# Sheet1.net
KiCad netlist of a schematic drawn in Altium Designer
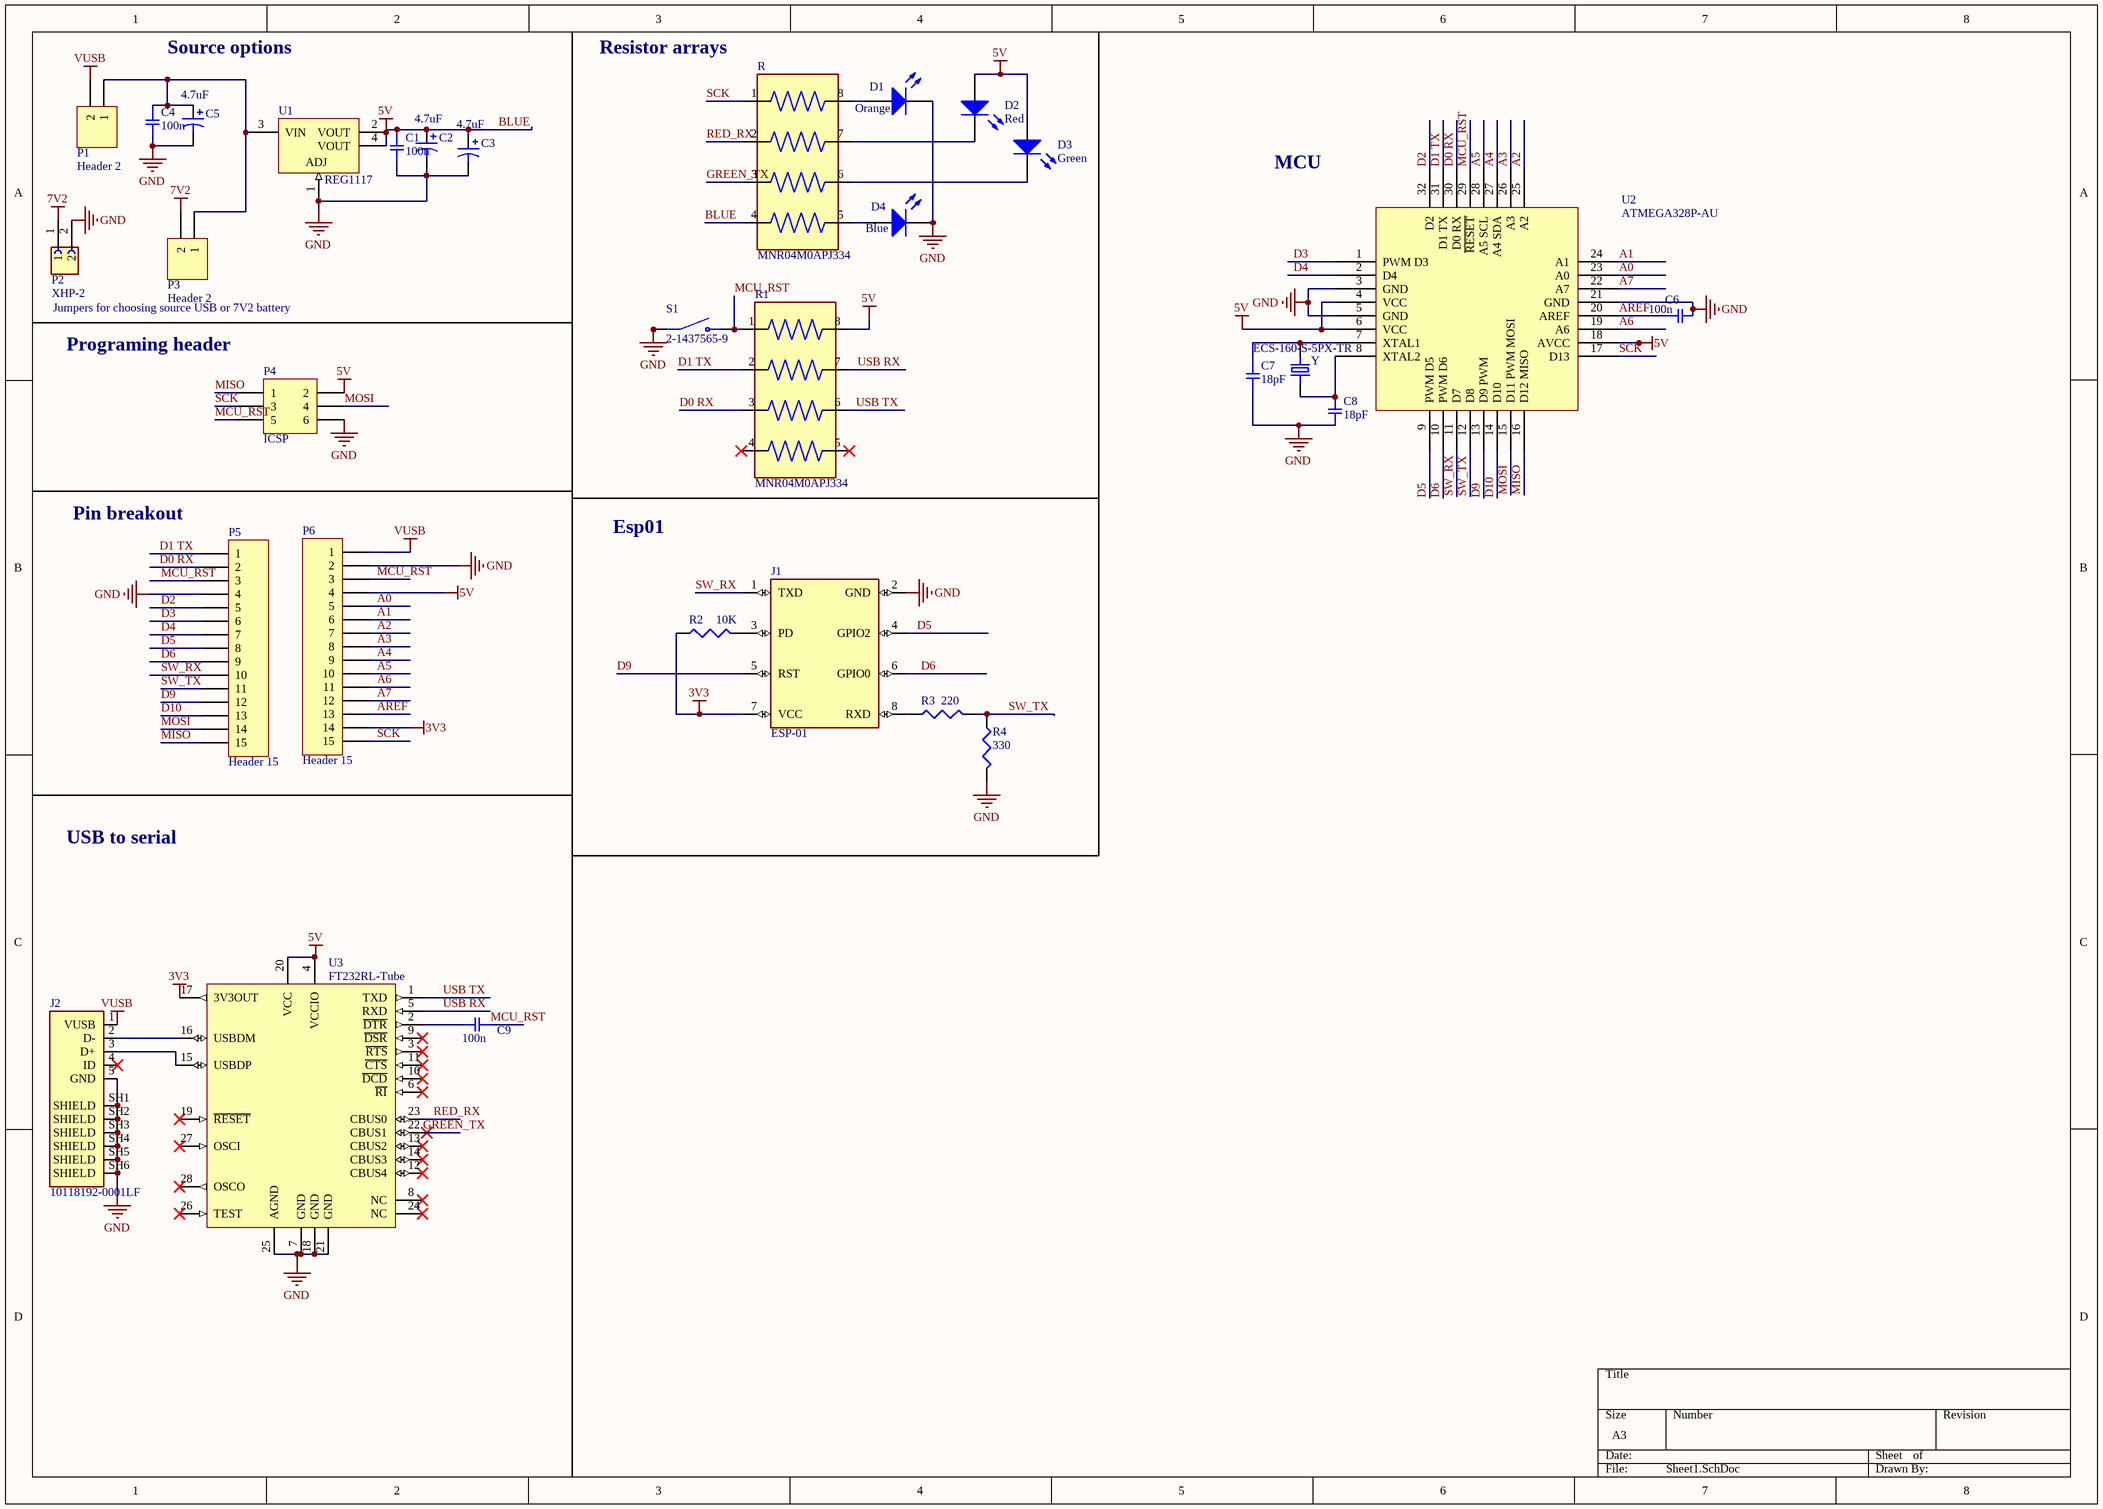
[diagram p0: Sheet1.SchDoc]

(export (version "E")
  (design (tool "Eeschema 10.0.6"))
  (components
    (comp (ref "C1")
      (value "100n")
      (footprint "SMD-0805C")
      (description "CAP CER 18PF 100V NP0 0805")
      (fields
        (field (name "DIGI-KEY PART NUMBER") "490-3606-1-ND")
        (field (name "PART NUMBER") "GQM2195C2A180JB01D")
      )
      (libsource (lib "capacitor_murata_0805") (part "GQM2195C2A180JB01D"))
    )
    (comp (ref "C2")
      (value "4.7uF")
      (footprint "49BC-E")
      (fields (field (name "Comment") "49BC475B010M") (field (name "PUBLISHER") "Altium Limited"))
      (libsource (lib "Vishay Sprague Tantalum Chip Capacitor") (part "49BC475B010M"))
    )
    (comp (ref "C3")
      (value "4.7uF")
      (footprint "49BC-E")
      (fields (field (name "Comment") "49BC475B010M") (field (name "PUBLISHER") "Altium Limited"))
      (libsource (lib "Vishay Sprague Tantalum Chip Capacitor") (part "49BC475B010M"))
    )
    (comp (ref "C4")
      (value "100n")
      (footprint "SMD-0805C")
      (description "CAP CER 18PF 100V NP0 0805")
      (fields
        (field (name "DIGI-KEY PART NUMBER") "490-3606-1-ND")
        (field (name "PART NUMBER") "GQM2195C2A180JB01D")
      )
      (libsource (lib "capacitor_murata_0805") (part "GQM2195C2A180JB01D"))
    )
    (comp (ref "C5")
      (value "4.7uF")
      (footprint "49BC-E")
      (fields (field (name "Comment") "49BC475B010M") (field (name "PUBLISHER") "Altium Limited"))
      (libsource (lib "Vishay Sprague Tantalum Chip Capacitor") (part "49BC475B010M"))
    )
    (comp (ref "C6")
      (value "100n")
      (footprint "SMD-0805C")
      (description "CAP CER 18PF 100V NP0 0805")
      (fields
        (field (name "DIGI-KEY PART NUMBER") "490-3606-1-ND")
        (field (name "PART NUMBER") "GQM2195C2A180JB01D")
      )
      (libsource (lib "capacitor_murata_0805") (part "GQM2195C2A180JB01D"))
    )
    (comp (ref "C7")
      (value "18pF")
      (footprint "SMD-0805C")
      (description "CAP CER 18PF 100V NP0 0805")
      (fields
        (field (name "DIGI-KEY PART NUMBER") "490-3606-1-ND")
        (field (name "PART NUMBER") "GQM2195C2A180JB01D")
      )
      (libsource (lib "capacitor_murata_0805") (part "GQM2195C2A180JB01D"))
    )
    (comp (ref "C8")
      (value "18pF")
      (footprint "SMD-0805C")
      (description "CAP CER 18PF 100V NP0 0805")
      (fields
        (field (name "DIGI-KEY PART NUMBER") "490-3606-1-ND")
        (field (name "PART NUMBER") "GQM2195C2A180JB01D")
      )
      (libsource (lib "capacitor_murata_0805") (part "GQM2195C2A180JB01D"))
    )
    (comp (ref "C9")
      (value "100n")
      (footprint "SMD-0805C")
      (description "CAP CER 18PF 100V NP0 0805")
      (fields
        (field (name "DIGI-KEY PART NUMBER") "490-3606-1-ND")
        (field (name "PART NUMBER") "GQM2195C2A180JB01D")
      )
      (libsource (lib "capacitor_murata_0805") (part "GQM2195C2A180JB01D"))
    )
    (comp (ref "D1")
      (value "Orange")
      (footprint "2.0X1.25X0.8")
      (fields (field (name "PUBLISHER") "Altium Limited"))
      (libsource (lib "Avago Optoelectronic LED") (part "HSMQ-C170"))
    )
    (comp (ref "D2")
      (value "Red")
      (footprint "2.0X1.25X0.8")
      (description "SMT Top Mount Chip LED, Green")
      (fields (field (name "PUBLISHER") "Altium Limited"))
      (libsource (lib "Avago Optoelectronic LED") (part "HSMQ-C170"))
    )
    (comp (ref "D3")
      (value "Green")
      (footprint "2.0X1.25X0.8")
      (description "SMT Top Mount Chip LED, Green")
      (fields (field (name "PUBLISHER") "Altium Limited"))
      (libsource (lib "Avago Optoelectronic LED") (part "HSMQ-C170"))
    )
    (comp (ref "D4")
      (value "Blue")
      (footprint "2.0X1.25X0.8")
      (description "SMT Top Mount Chip LED, Green")
      (fields (field (name "PUBLISHER") "Altium Limited"))
      (libsource (lib "Avago Optoelectronic LED") (part "HSMQ-C170"))
    )
    (comp (ref "J1")
      (value "ESP-01")
      (footprint "ESP-01:ESP-01")
      (description "ESP-01M ESP8266 DIP Adapter series Transceiver; 802.11 b/g/n (Wi-Fi, WiFi, WLAN) Evaluation Board")
      (fields (field (name "MF") "AI-Thinker"))
      (libsource (lib "ESP-01") (part "ESP-01"))
    )
    (comp (ref "J2")
      (value "10118192-0001LF")
      (footprint "AMPHENOL_10118192-0001LF")
      (description "Micro USB, Input Output Connectors, B TYPE RECEPTACLE with flange")
      (fields (field (name "MF") "AMPHENOL ICC / FCI"))
      (libsource (lib "10118192-0001LF") (part "10118192-0001LF"))
    )
    (comp (ref "P1")
      (value "Header 2")
      (footprint "HDR1X2")
      (description "Header, 2-Pin")
      (fields (field (name "PUBLISHER") "Altium Limited"))
      (libsource (lib "Miscellaneous Connectors") (part "Header 2"))
    )
    (comp (ref "P2")
      (value "XHP-2")
      (footprint "JST_XHP-2")
      (description "XH Series 2 Position 2.5 mm Pitch Wire-to-Board Housing Connector")
      (libsource (lib "XHP-2") (part "XHP-2"))
    )
    (comp (ref "P3")
      (value "Header 2")
      (footprint "HDR1X2")
      (description "Header, 2-Pin")
      (fields (field (name "PUBLISHER") "Altium Limited"))
      (libsource (lib "Miscellaneous Connectors") (part "Header 2"))
    )
    (comp (ref "P4")
      (value "ICSP")
      (footprint "HDR2X3")
      (description "Header, 3-Pin, Dual row")
      (fields (field (name "PUBLISHER") "Altium Limited"))
      (libsource (lib "Miscellaneous Connectors") (part "Header 3X2"))
    )
    (comp (ref "P5")
      (value "Header 15")
      (footprint "HDR1X15")
      (description "Header, 15-Pin")
      (fields (field (name "PUBLISHER") "Altium Limited"))
      (libsource (lib "Miscellaneous Connectors") (part "Header 15"))
    )
    (comp (ref "P6")
      (value "Header 15")
      (footprint "HDR1X15")
      (description "Header, 15-Pin")
      (fields (field (name "PUBLISHER") "Altium Limited"))
      (libsource (lib "") (part "Header 15_1"))
    )
    (comp (ref "R")
      (value "MNR04M0APJ334")
      (footprint "RESCAXS50P200X100X45-8N:RESCAXS50P200X100X45-8N")
      (description "Res Array 330K Ohm 5% Â±200ppm/Â°C ISOL Epoxy 8-Pin 0804(4 X 0402) Convex SMD Automotive T/R")
      (fields (field (name "MF") "Rohm"))
      (libsource (lib "MNR04M0APJ334") (part "MNR04M0APJ334"))
    )
    (comp (ref "R1")
      (value "MNR04M0APJ334")
      (footprint "RESCAXS50P200X100X45-8N:RESCAXS50P200X100X45-8N")
      (description "Res Array 330K Ohm 5% Â±200ppm/Â°C ISOL Epoxy 8-Pin 0804(4 X 0402) Convex SMD Automotive T/R")
      (fields (field (name "MF") "Rohm"))
      (libsource (lib "MNR04M0APJ334") (part "MNR04M0APJ334"))
    )
    (comp (ref "R2")
      (value "10K")
      (footprint "J1-0603")
      (description "Resistor")
      (fields (field (name "Comment") "Res3") (field (name "PUBLISHER") "Altium Limited"))
      (libsource (lib "Miscellaneous Devices") (part "Res3"))
    )
    (comp (ref "R3")
      (value "220")
      (footprint "J1-0603")
      (description "Resistor")
      (fields (field (name "Comment") "Res3") (field (name "PUBLISHER") "Altium Limited"))
      (libsource (lib "Miscellaneous Devices") (part "Res3"))
    )
    (comp (ref "R4")
      (value "330")
      (footprint "J1-0603")
      (description "Resistor")
      (fields (field (name "Comment") "Res3") (field (name "PUBLISHER") "Altium Limited"))
      (libsource (lib "Miscellaneous Devices") (part "Res3"))
    )
    (comp (ref "S1")
      (value "2-1437565-9")
      (footprint "SW_2-1437565-9")
      (fields (field (name "MF") "{'manufacturer': 'TE Connectivity'}"))
      (libsource (lib "2-1437565-9") (part "2-1437565-9"))
    )
    (comp (ref "U1")
      (value "REG1117")
      (footprint "TI-DCY4_N")
      (fields (field (name "MANUFACTURER") "Texas Instruments"))
      (libsource (lib "TI Power Management Linear Regulator Single Channel LDO (400-7500mA)") (part "REG1117"))
    )
    (comp (ref "U2")
      (value "ATMEGA328P-AU")
      (footprint "TQFP80P900X900X120-32N")
      (description "Microchip ATMEGA328P-AU, 8bit AVR Microcontroller, ATmega, 20MHz, 32 kB Flash, 32-Pin TQFP")
      (fields (field (name "CREATED BY") "Mariano Franceschetti"))
      (libsource (lib "AtmelMCU") (part "ATMEGA328P-AU"))
    )
    (comp (ref "U3")
      (value "FT232RL-Tube")
      (footprint "SSOP-28_N")
      (description "USB UART Asynchronous Serial Data Transfer Chip, SSOP-28, Tube")
      (fields (field (name "PUBLISHER") "Altium Limited"))
      (libsource (lib "FTDI Communication UART") (part "FT232RL-Tube"))
    )
    (comp (ref "Y")
      (value "ECS-160-S-5PX-TR")
      (footprint "SnapEDApcb:XTAL_ECS-160-S-5PX-TR")
      (description "16MHz Â±30ppm Crystal Series 40 Ohms HC-49/US")
      (fields (field (name "MF") "ECS Inc."))
      (libsource (lib "ECS-160-S-5PX-TR") (part "ECS-160-S-5PX-TR"))
    )
  )
  (nets
    (net (code "1") (name "/A0") (class "Default")
      (node (ref "P6") (pin "5") (pinfunction "5_5") (pintype "passive"))
      (node (ref "U2") (pin "23") (pinfunction "A0_23") (pintype "power_in"))
    )
    (net (code "2") (name "/A1") (class "Default")
      (node (ref "P6") (pin "6") (pinfunction "6_6") (pintype "passive"))
      (node (ref "U2") (pin "24") (pinfunction "A1_24") (pintype "power_in"))
    )
    (net (code "3") (name "/A2") (class "Default")
      (node (ref "P6") (pin "7") (pinfunction "7_7") (pintype "passive"))
      (node (ref "U2") (pin "25") (pinfunction "A2_25") (pintype "power_in"))
    )
    (net (code "4") (name "/A3") (class "Default")
      (node (ref "P6") (pin "8") (pinfunction "8_8") (pintype "passive"))
      (node (ref "U2") (pin "26") (pinfunction "A3_26") (pintype "power_in"))
    )
    (net (code "5") (name "/A4") (class "Default")
      (node (ref "P6") (pin "9") (pinfunction "9_9") (pintype "passive"))
      (node (ref "U2") (pin "27") (pinfunction "A4_SDA_27") (pintype "power_in"))
    )
    (net (code "6") (name "/A5") (class "Default")
      (node (ref "P6") (pin "10") (pinfunction "10_10") (pintype "passive"))
      (node (ref "U2") (pin "28") (pinfunction "A5_SCL_28") (pintype "power_in"))
    )
    (net (code "7") (name "/A6") (class "Default")
      (node (ref "P6") (pin "11") (pinfunction "11_11") (pintype "passive"))
      (node (ref "U2") (pin "19") (pinfunction "A6_19") (pintype "power_in"))
    )
    (net (code "8") (name "/A7") (class "Default")
      (node (ref "P6") (pin "12") (pinfunction "12_12") (pintype "passive"))
      (node (ref "U2") (pin "22") (pinfunction "A7_22") (pintype "power_in"))
    )
    (net (code "9") (name "/AREF") (class "Default")
      (node (ref "C6") (pin "1") (pinfunction "1_1") (pintype "passive"))
      (node (ref "P6") (pin "13") (pinfunction "13_13") (pintype "passive"))
      (node (ref "U2") (pin "20") (pinfunction "AREF_20") (pintype "power_in"))
    )
    (net (code "10") (name "/D0 RX") (class "Default")
      (node (ref "P5") (pin "2") (pinfunction "2_2") (pintype "passive"))
      (node (ref "R1") (pin "3") (pinfunction "3_3") (pintype "passive"))
      (node (ref "U2") (pin "30") (pinfunction "D0_RX_30") (pintype "power_in"))
    )
    (net (code "11") (name "/D1 TX") (class "Default")
      (node (ref "P5") (pin "1") (pinfunction "1_1") (pintype "passive"))
      (node (ref "R1") (pin "2") (pinfunction "2_2") (pintype "passive"))
      (node (ref "U2") (pin "31") (pinfunction "D1_TX_31") (pintype "power_in"))
    )
    (net (code "12") (name "/D2") (class "Default")
      (node (ref "P5") (pin "5") (pinfunction "5_5") (pintype "passive"))
      (node (ref "U2") (pin "32") (pinfunction "D2_32") (pintype "power_in"))
    )
    (net (code "13") (name "/D3") (class "Default")
      (node (ref "P5") (pin "6") (pinfunction "6_6") (pintype "passive"))
      (node (ref "U2") (pin "1") (pinfunction "PWM_D3_1") (pintype "power_in"))
    )
    (net (code "14") (name "/D4") (class "Default")
      (node (ref "P5") (pin "7") (pinfunction "7_7") (pintype "passive"))
      (node (ref "U2") (pin "2") (pinfunction "D4_2") (pintype "power_in"))
    )
    (net (code "15") (name "/D5") (class "Default")
      (node (ref "J1") (pin "4") (pinfunction "GPIO2_4") (pintype "bidirectional"))
      (node (ref "P5") (pin "8") (pinfunction "8_8") (pintype "passive"))
      (node (ref "U2") (pin "9") (pinfunction "PWM_D5_9") (pintype "power_in"))
    )
    (net (code "16") (name "/D6") (class "Default")
      (node (ref "J1") (pin "6") (pinfunction "GPIO0_6") (pintype "bidirectional"))
      (node (ref "P5") (pin "9") (pinfunction "9_9") (pintype "passive"))
      (node (ref "U2") (pin "10") (pinfunction "PWM_D6_10") (pintype "power_in"))
    )
    (net (code "17") (name "/D9") (class "Default")
      (node (ref "J1") (pin "5") (pinfunction "RST_5") (pintype "bidirectional"))
      (node (ref "P5") (pin "12") (pinfunction "12_12") (pintype "passive"))
      (node (ref "U2") (pin "13") (pinfunction "D9_PWM_13") (pintype "power_in"))
    )
    (net (code "18") (name "/D10") (class "Default")
      (node (ref "P5") (pin "13") (pinfunction "13_13") (pintype "passive"))
      (node (ref "U2") (pin "14") (pinfunction "D10_14") (pintype "power_in"))
    )
    (net (code "19") (name "/GREEN_TX") (class "Default")
      (node (ref "R") (pin "3") (pinfunction "3_3") (pintype "passive"))
      (node (ref "U3") (pin "22") (pinfunction "CBUS1_22") (pintype "bidirectional"))
    )
    (net (code "20") (name "/MCU_RST") (class "Default")
      (node (ref "C9") (pin "2") (pinfunction "2_2") (pintype "passive"))
      (node (ref "P4") (pin "5") (pinfunction "5_5") (pintype "passive"))
      (node (ref "P5") (pin "3") (pinfunction "3_3") (pintype "passive"))
      (node (ref "P6") (pin "3") (pinfunction "3_3") (pintype "passive"))
      (node (ref "R1") (pin "1") (pinfunction "1_1") (pintype "passive"))
      (node (ref "S1") (pin "3") (pinfunction "NO_3") (pintype "passive"))
      (node (ref "S1") (pin "4") (pinfunction "NO_4") (pintype "passive"))
      (node (ref "U2") (pin "29") (pinfunction "~{RESET}_29") (pintype "power_in"))
    )
    (net (code "21") (name "/MISO") (class "Default")
      (node (ref "P4") (pin "1") (pinfunction "1_1") (pintype "passive"))
      (node (ref "P5") (pin "15") (pinfunction "15_15") (pintype "passive"))
      (node (ref "U2") (pin "16") (pinfunction "D12_MISO_16") (pintype "power_in"))
    )
    (net (code "22") (name "/MOSI") (class "Default")
      (node (ref "P4") (pin "4") (pinfunction "4_4") (pintype "passive"))
      (node (ref "P5") (pin "14") (pinfunction "14_14") (pintype "passive"))
      (node (ref "U2") (pin "15") (pinfunction "D11_PWM_MOSI_15") (pintype "power_in"))
    )
    (net (code "23") (name "/RED_RX") (class "Default")
      (node (ref "R") (pin "2") (pinfunction "2_2") (pintype "passive"))
      (node (ref "U3") (pin "23") (pinfunction "CBUS0_23") (pintype "bidirectional"))
    )
    (net (code "24") (name "/SCK") (class "Default")
      (node (ref "P4") (pin "3") (pinfunction "3_3") (pintype "passive"))
      (node (ref "P6") (pin "15") (pinfunction "15_15") (pintype "passive"))
      (node (ref "R") (pin "1") (pinfunction "1_1") (pintype "passive"))
      (node (ref "U2") (pin "17") (pinfunction "D13_17") (pintype "power_in"))
    )
    (net (code "25") (name "/SW_RX") (class "Default")
      (node (ref "J1") (pin "1") (pinfunction "TXD_1") (pintype "bidirectional"))
      (node (ref "P5") (pin "10") (pinfunction "10_10") (pintype "passive"))
      (node (ref "U2") (pin "11") (pinfunction "D7_11") (pintype "power_in"))
    )
    (net (code "26") (name "/SW_TX") (class "Default")
      (node (ref "P5") (pin "11") (pinfunction "11_11") (pintype "passive"))
      (node (ref "R3") (pin "2") (pinfunction "2_2") (pintype "passive"))
      (node (ref "R4") (pin "1") (pinfunction "1_1") (pintype "passive"))
      (node (ref "U2") (pin "12") (pinfunction "D8_12") (pintype "power_in"))
    )
    (net (code "27") (name "/USB RX") (class "Default")
      (node (ref "R1") (pin "7") (pinfunction "7_7") (pintype "passive"))
      (node (ref "U3") (pin "5") (pinfunction "RXD_5") (pintype "input"))
    )
    (net (code "28") (name "/USB TX") (class "Default")
      (node (ref "R1") (pin "6") (pinfunction "6_6") (pintype "passive"))
      (node (ref "U3") (pin "1") (pinfunction "TXD_1") (pintype "output"))
    )
    (net (code "29") (name "3V3") (class "Default")
      (node (ref "J1") (pin "7") (pinfunction "VCC_7") (pintype "bidirectional"))
      (node (ref "P6") (pin "14") (pinfunction "14_14") (pintype "passive"))
      (node (ref "R2") (pin "1") (pinfunction "1_1") (pintype "passive"))
      (node (ref "U3") (pin "17") (pinfunction "3V3OUT_17") (pintype "output"))
    )
    (net (code "30") (name "5V") (class "Default")
      (node (ref "C1") (pin "1") (pinfunction "1_1") (pintype "passive"))
      (node (ref "C2") (pin "1") (pinfunction "1_1") (pintype "passive"))
      (node (ref "C3") (pin "1") (pinfunction "1_1") (pintype "passive"))
      (node (ref "D2") (pin "1") (pinfunction "A_1") (pintype "passive"))
      (node (ref "D3") (pin "1") (pinfunction "A_1") (pintype "passive"))
      (node (ref "P4") (pin "2") (pinfunction "2_2") (pintype "passive"))
      (node (ref "P6") (pin "4") (pinfunction "4_4") (pintype "passive"))
      (node (ref "R") (pin "4") (pinfunction "4_4") (pintype "passive"))
      (node (ref "R1") (pin "8") (pinfunction "8_8") (pintype "passive"))
      (node (ref "U1") (pin "2") (pinfunction "VOUT_2") (pintype "power_in"))
      (node (ref "U1") (pin "4") (pinfunction "VOUT_4") (pintype "power_in"))
      (node (ref "U2") (pin "18") (pinfunction "AVCC_18") (pintype "power_in"))
      (node (ref "U2") (pin "4") (pinfunction "VCC_4") (pintype "power_in"))
      (node (ref "U2") (pin "6") (pinfunction "VCC_6") (pintype "power_in"))
      (node (ref "U3") (pin "20") (pinfunction "VCC_20") (pintype "power_in"))
      (node (ref "U3") (pin "4") (pinfunction "VCCIO_4") (pintype "power_in"))
    )
    (net (code "31") (name "7V2") (class "Default")
      (node (ref "P2") (pin "1") (pinfunction "1_1") (pintype "passive"))
      (node (ref "P3") (pin "2") (pinfunction "2_2") (pintype "passive"))
    )
    (net (code "32") (name "GND") (class "Default")
      (node (ref "C1") (pin "2") (pinfunction "2_2") (pintype "passive"))
      (node (ref "C2") (pin "2") (pinfunction "2_2") (pintype "passive"))
      (node (ref "C3") (pin "2") (pinfunction "2_2") (pintype "passive"))
      (node (ref "C4") (pin "2") (pinfunction "2_2") (pintype "passive"))
      (node (ref "C5") (pin "2") (pinfunction "2_2") (pintype "passive"))
      (node (ref "C6") (pin "2") (pinfunction "2_2") (pintype "passive"))
      (node (ref "C7") (pin "2") (pinfunction "2_2") (pintype "passive"))
      (node (ref "C8") (pin "2") (pinfunction "2_2") (pintype "passive"))
      (node (ref "D1") (pin "2") (pinfunction "K_2") (pintype "passive"))
      (node (ref "D4") (pin "2") (pinfunction "K_2") (pintype "passive"))
      (node (ref "J1") (pin "2") (pinfunction "GND_2") (pintype "bidirectional"))
      (node (ref "J2") (pin "5") (pinfunction "GND_5") (pintype "passive"))
      (node (ref "J2") (pin "SH1") (pinfunction "SHIELD_SH1") (pintype "passive"))
      (node (ref "J2") (pin "SH2") (pinfunction "SHIELD_SH2") (pintype "passive"))
      (node (ref "J2") (pin "SH3") (pinfunction "SHIELD_SH3") (pintype "passive"))
      (node (ref "J2") (pin "SH4") (pinfunction "SHIELD_SH4") (pintype "passive"))
      (node (ref "J2") (pin "SH5") (pinfunction "SHIELD_SH5") (pintype "passive"))
      (node (ref "J2") (pin "SH6") (pinfunction "SHIELD_SH6") (pintype "passive"))
      (node (ref "P2") (pin "2") (pinfunction "2_2") (pintype "passive"))
      (node (ref "P4") (pin "6") (pinfunction "6_6") (pintype "passive"))
      (node (ref "P5") (pin "4") (pinfunction "4_4") (pintype "passive"))
      (node (ref "P6") (pin "2") (pinfunction "2_2") (pintype "passive"))
      (node (ref "R4") (pin "2") (pinfunction "2_2") (pintype "passive"))
      (node (ref "S1") (pin "1") (pinfunction "COM_1") (pintype "passive"))
      (node (ref "S1") (pin "2") (pinfunction "COM_2") (pintype "passive"))
      (node (ref "U1") (pin "1") (pinfunction "ADJ_1") (pintype "input"))
      (node (ref "U2") (pin "21") (pinfunction "GND_21") (pintype "power_in"))
      (node (ref "U2") (pin "3") (pinfunction "GND_3") (pintype "power_in"))
      (node (ref "U2") (pin "5") (pinfunction "GND_5") (pintype "power_in"))
      (node (ref "U3") (pin "18") (pinfunction "GND_18") (pintype "power_in"))
      (node (ref "U3") (pin "21") (pinfunction "GND_21") (pintype "power_in"))
      (node (ref "U3") (pin "25") (pinfunction "AGND_25") (pintype "power_in"))
      (node (ref "U3") (pin "7") (pinfunction "GND_7") (pintype "power_in"))
    )
    (net (code "33") (name "Net-(D1-A)") (class "Default")
      (node (ref "D1") (pin "1") (pinfunction "A_1") (pintype "passive"))
      (node (ref "R") (pin "8") (pinfunction "8_8") (pintype "passive"))
    )
    (net (code "34") (name "Net-(D2-K)") (class "Default")
      (node (ref "D2") (pin "2") (pinfunction "K_2") (pintype "passive"))
      (node (ref "R") (pin "7") (pinfunction "7_7") (pintype "passive"))
    )
    (net (code "35") (name "Net-(D3-K)") (class "Default")
      (node (ref "D3") (pin "2") (pinfunction "K_2") (pintype "passive"))
      (node (ref "R") (pin "6") (pinfunction "6_6") (pintype "passive"))
    )
    (net (code "36") (name "Net-(D4-A)") (class "Default")
      (node (ref "D4") (pin "1") (pinfunction "A_1") (pintype "passive"))
      (node (ref "R") (pin "5") (pinfunction "5_5") (pintype "passive"))
    )
    (net (code "37") (name "Net-(J1-PD)") (class "Default")
      (node (ref "J1") (pin "3") (pinfunction "PD_3") (pintype "bidirectional"))
      (node (ref "R2") (pin "2") (pinfunction "2_2") (pintype "passive"))
    )
    (net (code "38") (name "Net-(J1-RXD)") (class "Default")
      (node (ref "J1") (pin "8") (pinfunction "RXD_8") (pintype "bidirectional"))
      (node (ref "R3") (pin "1") (pinfunction "1_1") (pintype "passive"))
    )
    (net (code "39") (name "Net-(J2-D+)") (class "Default")
      (node (ref "J2") (pin "3") (pinfunction "D+_3") (pintype "passive"))
      (node (ref "U3") (pin "15") (pinfunction "USBDP_15") (pintype "bidirectional"))
    )
    (net (code "40") (name "Net-(J2-D-)") (class "Default")
      (node (ref "J2") (pin "2") (pinfunction "D-_2") (pintype "passive"))
      (node (ref "U3") (pin "16") (pinfunction "USBDM_16") (pintype "bidirectional"))
    )
    (net (code "41") (name "Net-(U1-VIN)") (class "Default")
      (node (ref "C4") (pin "1") (pinfunction "1_1") (pintype "passive"))
      (node (ref "C5") (pin "1") (pinfunction "1_1") (pintype "passive"))
      (node (ref "P1") (pin "1") (pinfunction "1_1") (pintype "passive"))
      (node (ref "P3") (pin "1") (pinfunction "1_1") (pintype "passive"))
      (node (ref "U1") (pin "3") (pinfunction "VIN_3") (pintype "power_in"))
    )
    (net (code "42") (name "Net-(U2-XTAL1)") (class "Default")
      (node (ref "C7") (pin "1") (pinfunction "1_1") (pintype "passive"))
      (node (ref "U2") (pin "7") (pinfunction "XTAL1_7") (pintype "power_in"))
      (node (ref "Y") (pin "2") (pinfunction "2_2") (pintype "passive"))
    )
    (net (code "43") (name "Net-(U2-XTAL2)") (class "Default")
      (node (ref "C8") (pin "1") (pinfunction "1_1") (pintype "passive"))
      (node (ref "U2") (pin "8") (pinfunction "XTAL2_8") (pintype "power_in"))
      (node (ref "Y") (pin "1") (pinfunction "1_1") (pintype "passive"))
    )
    (net (code "44") (name "Net-(U3-~{DTR})") (class "Default")
      (node (ref "C9") (pin "1") (pinfunction "1_1") (pintype "passive"))
      (node (ref "U3") (pin "2") (pinfunction "~{DTR}_2") (pintype "output"))
    )
    (net (code "45") (name "VUSB") (class "Default")
      (node (ref "J2") (pin "1") (pinfunction "VUSB_1") (pintype "passive"))
      (node (ref "P1") (pin "2") (pinfunction "2_2") (pintype "passive"))
      (node (ref "P6") (pin "1") (pinfunction "1_1") (pintype "passive"))
    )
    (net (code "46") (name "unconnected-(J2-ID-Pad4)") (class "Default")
      (node (ref "J2") (pin "4") (pinfunction "ID_4") (pintype "passive+no_connect"))
    )
    (net (code "47") (name "unconnected-(R1-Pad4)") (class "Default")
      (node (ref "R1") (pin "4") (pinfunction "4_4") (pintype "passive+no_connect"))
    )
    (net (code "48") (name "unconnected-(R1-Pad5)") (class "Default")
      (node (ref "R1") (pin "5") (pinfunction "5_5") (pintype "passive+no_connect"))
    )
    (net (code "49") (name "unconnected-(U3-CBUS2-Pad13)") (class "Default")
      (node (ref "U3") (pin "13") (pinfunction "CBUS2_13") (pintype "bidirectional+no_connect"))
    )
    (net (code "50") (name "unconnected-(U3-CBUS3-Pad14)") (class "Default")
      (node (ref "U3") (pin "14") (pinfunction "CBUS3_14") (pintype "bidirectional+no_connect"))
    )
    (net (code "51") (name "unconnected-(U3-CBUS4-Pad12)") (class "Default")
      (node (ref "U3") (pin "12") (pinfunction "CBUS4_12") (pintype "bidirectional+no_connect"))
    )
    (net (code "52") (name "unconnected-(U3-NC-Pad8)") (class "Default")
      (node (ref "U3") (pin "8") (pinfunction "NC_8") (pintype "passive+no_connect"))
    )
    (net (code "53") (name "unconnected-(U3-NC-Pad24)") (class "Default")
      (node (ref "U3") (pin "24") (pinfunction "NC_24") (pintype "passive+no_connect"))
    )
    (net (code "54") (name "unconnected-(U3-OSCI-Pad27)") (class "Default")
      (node (ref "U3") (pin "27") (pinfunction "OSCI_27") (pintype "input+no_connect"))
    )
    (net (code "55") (name "unconnected-(U3-OSCO-Pad28)") (class "Default")
      (node (ref "U3") (pin "28") (pinfunction "OSCO_28") (pintype "output+no_connect"))
    )
    (net (code "56") (name "unconnected-(U3-TEST-Pad26)") (class "Default")
      (node (ref "U3") (pin "26") (pinfunction "TEST_26") (pintype "input+no_connect"))
    )
    (net (code "57") (name "unconnected-(U3-~{CTS}-Pad11)") (class "Default")
      (node (ref "U3") (pin "11") (pinfunction "~{CTS}_11") (pintype "input+no_connect"))
    )
    (net (code "58") (name "unconnected-(U3-~{DCD}-Pad10)") (class "Default")
      (node (ref "U3") (pin "10") (pinfunction "~{DCD}_10") (pintype "input+no_connect"))
    )
    (net (code "59") (name "unconnected-(U3-~{DSR}-Pad9)") (class "Default")
      (node (ref "U3") (pin "9") (pinfunction "~{DSR}_9") (pintype "input+no_connect"))
    )
    (net (code "60") (name "unconnected-(U3-~{RESET}-Pad19)") (class "Default")
      (node (ref "U3") (pin "19") (pinfunction "~{RESET}_19") (pintype "input+no_connect"))
    )
    (net (code "61") (name "unconnected-(U3-~{RI}-Pad6)") (class "Default")
      (node (ref "U3") (pin "6") (pinfunction "~{RI}_6") (pintype "input+no_connect"))
    )
    (net (code "62") (name "unconnected-(U3-~{RTS}-Pad3)") (class "Default")
      (node (ref "U3") (pin "3") (pinfunction "~{RTS}_3") (pintype "output+no_connect"))
    )
  )
)
